# nucleum.net
KiCad netlist of a schematic drawn in EAGLE
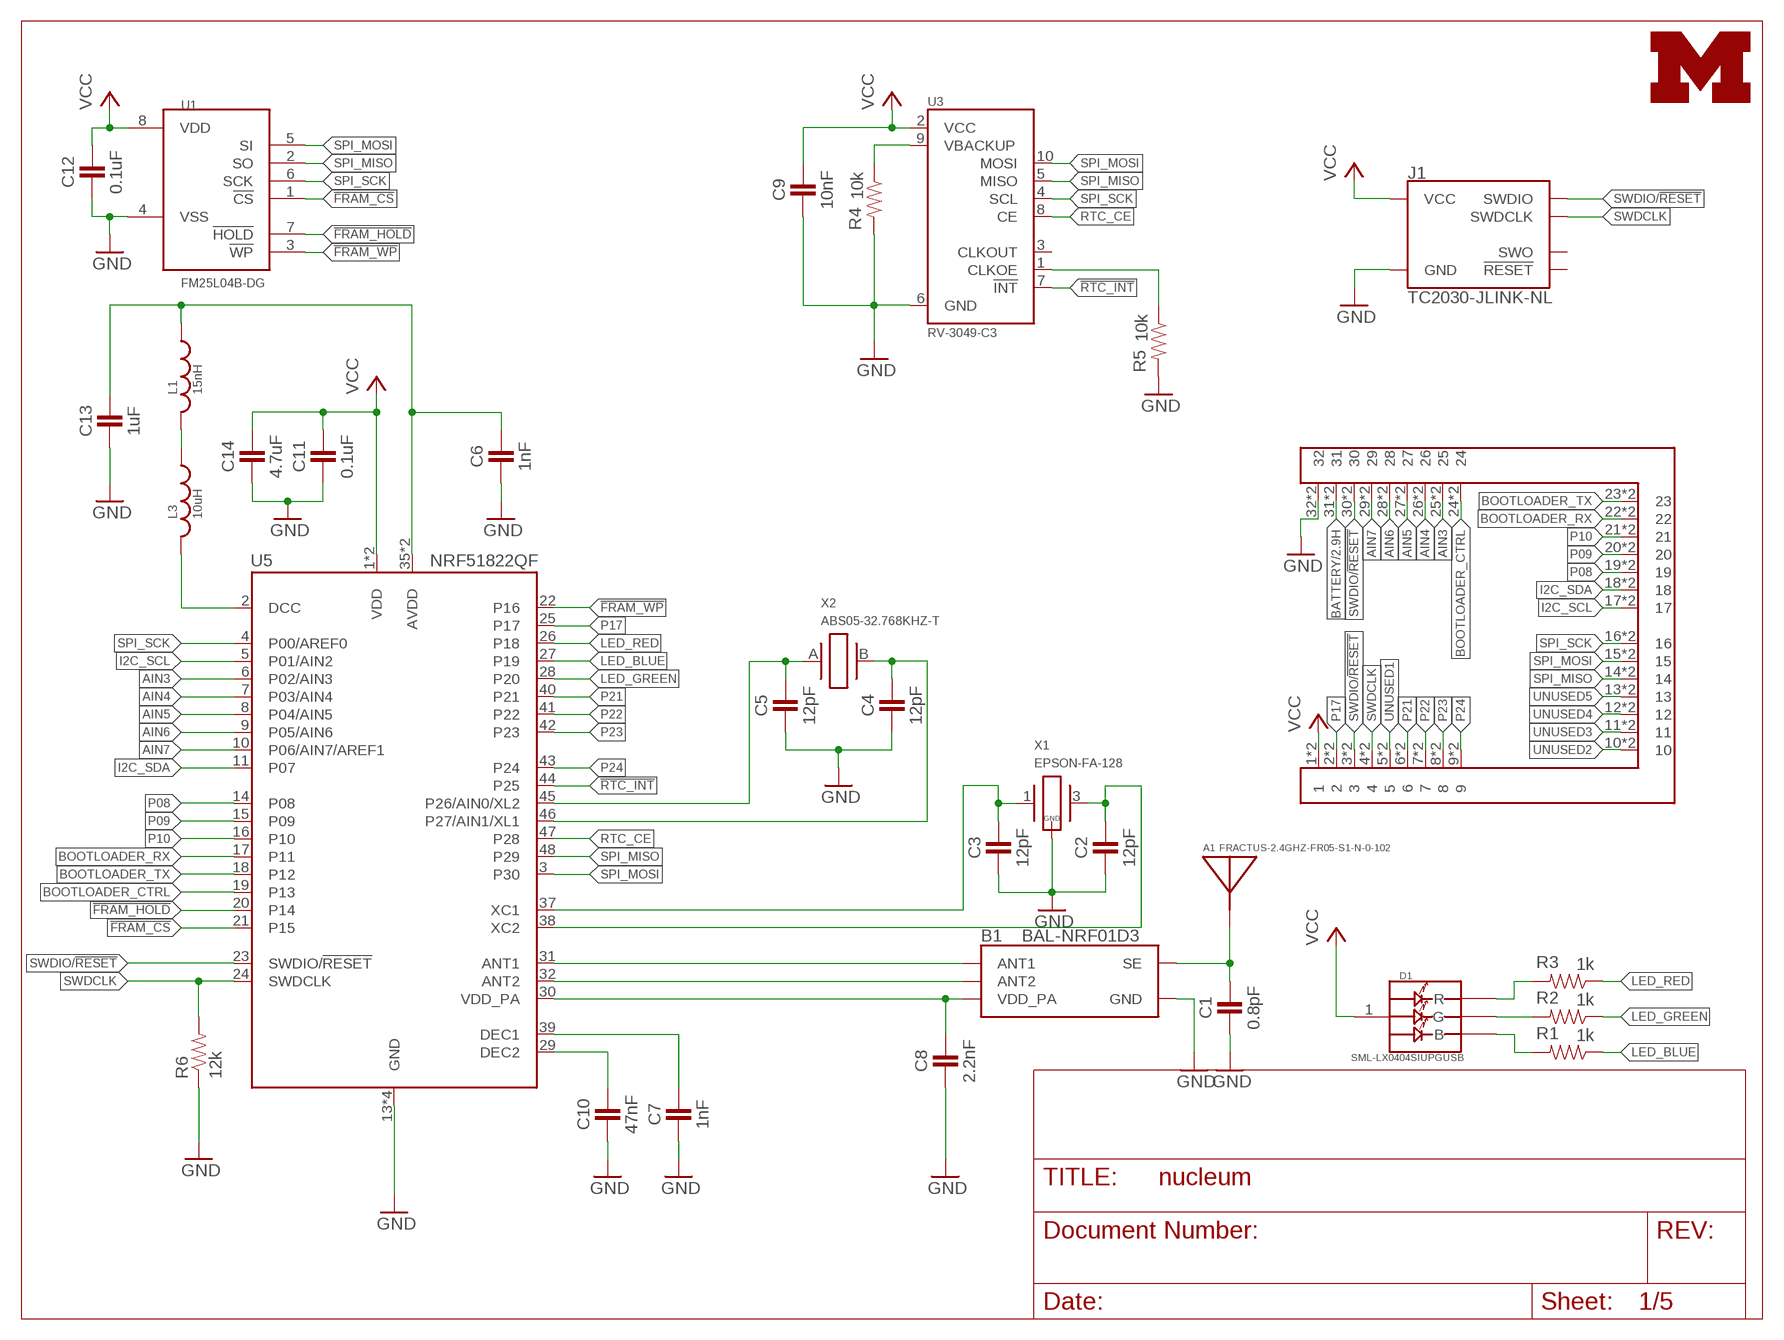
[diagram p0: schematic, sheet 1]
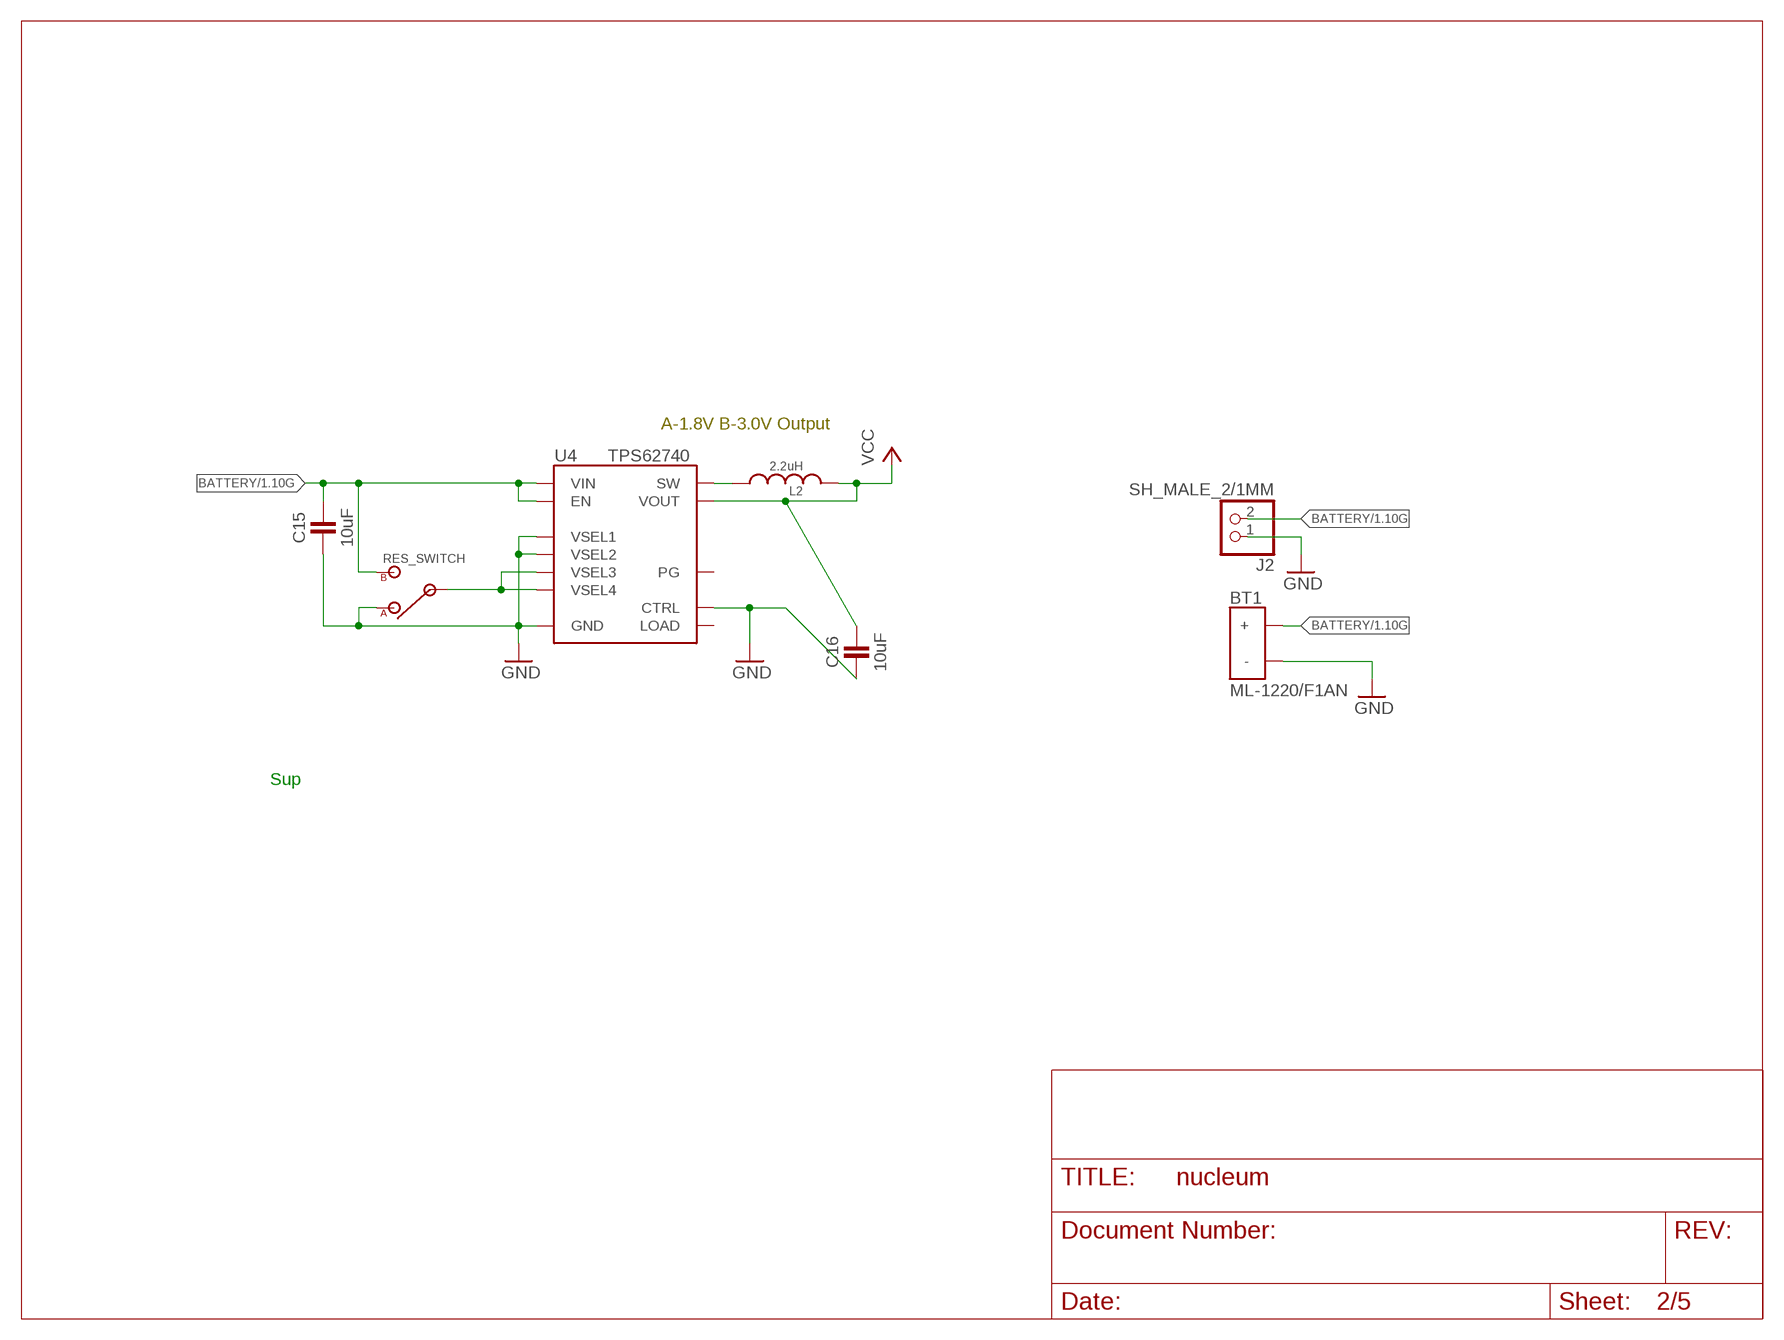
[diagram p1: schematic, sheet 2]
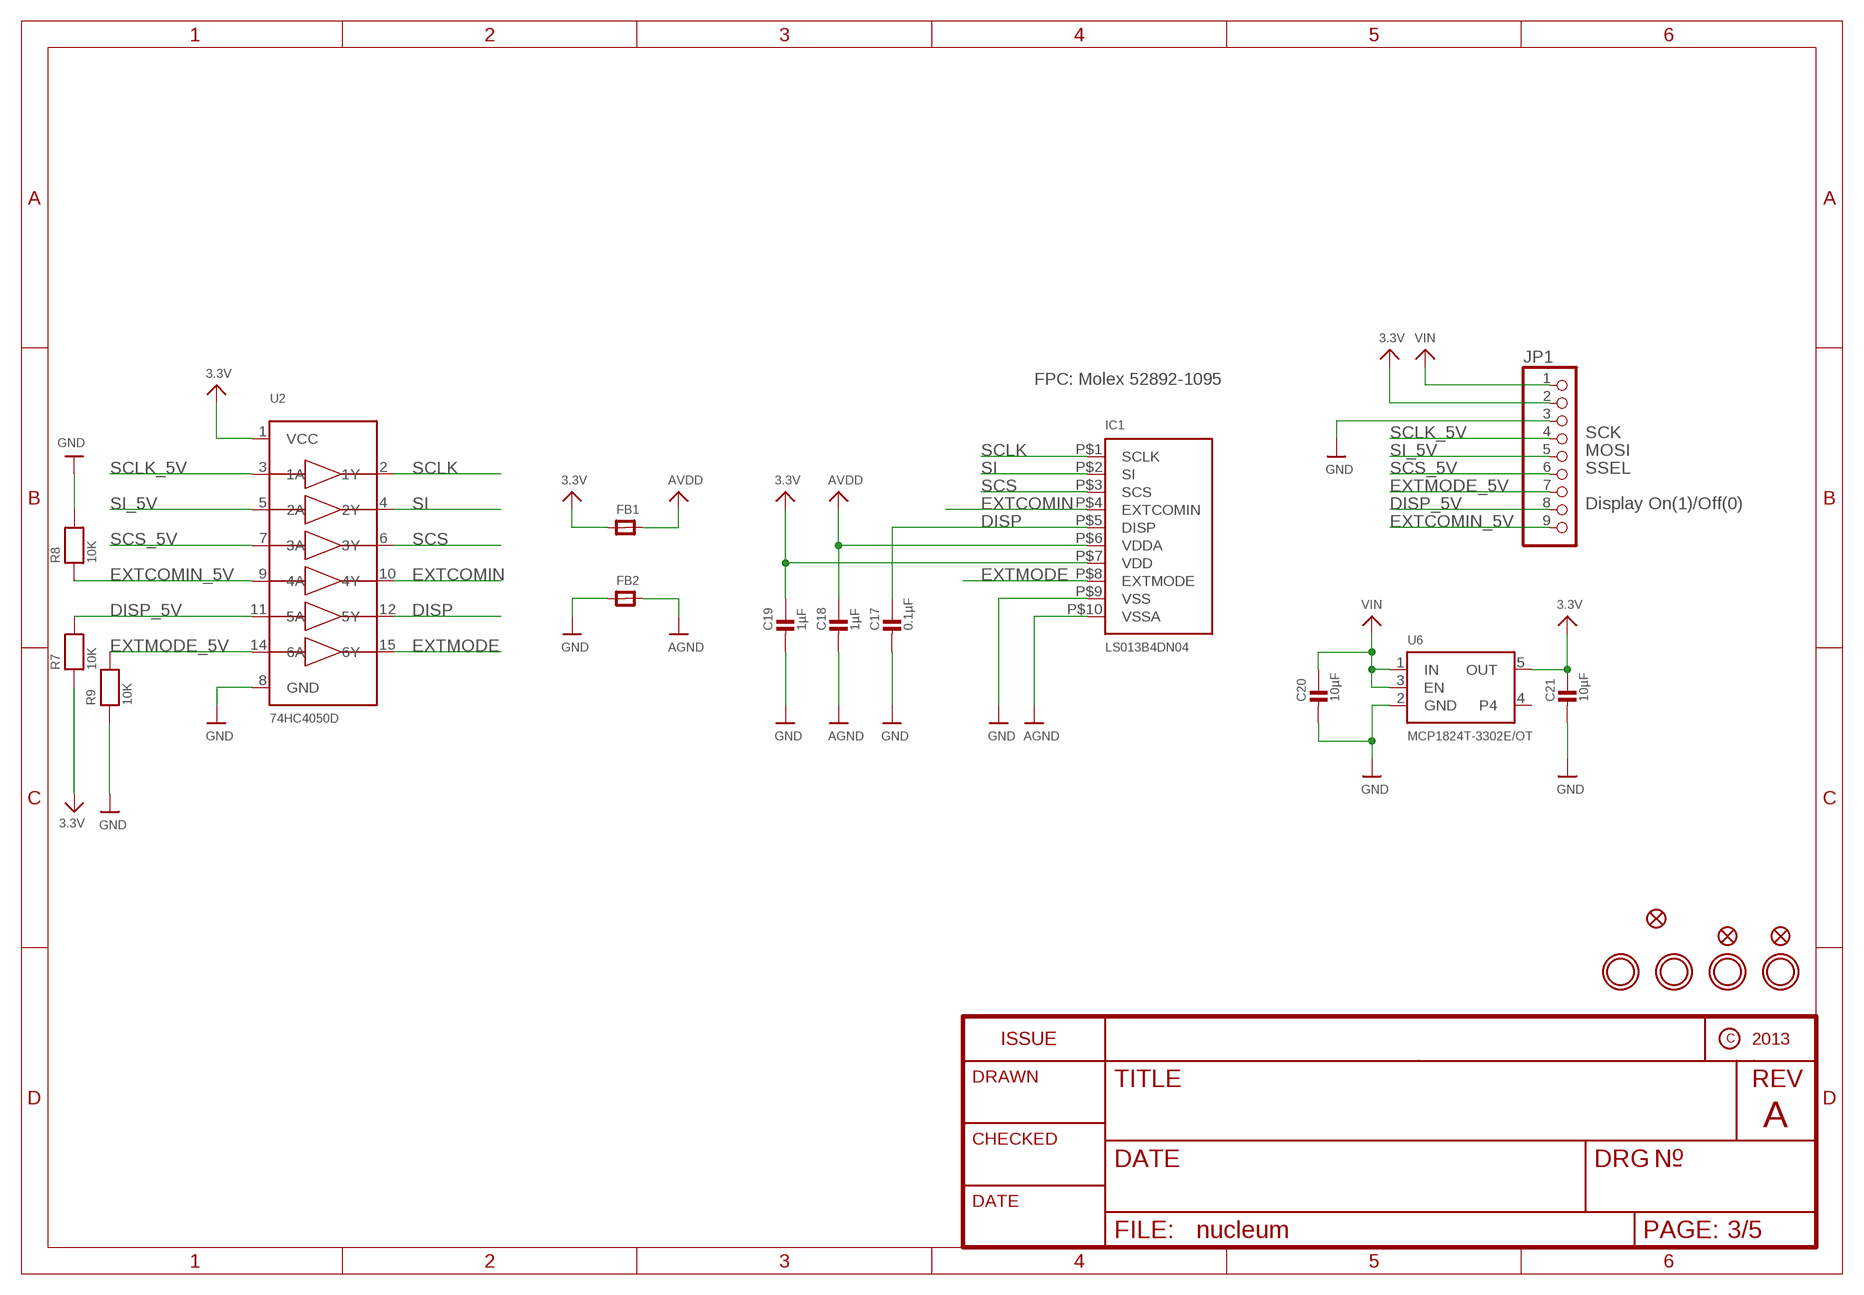
[diagram p2: schematic, sheet 3]
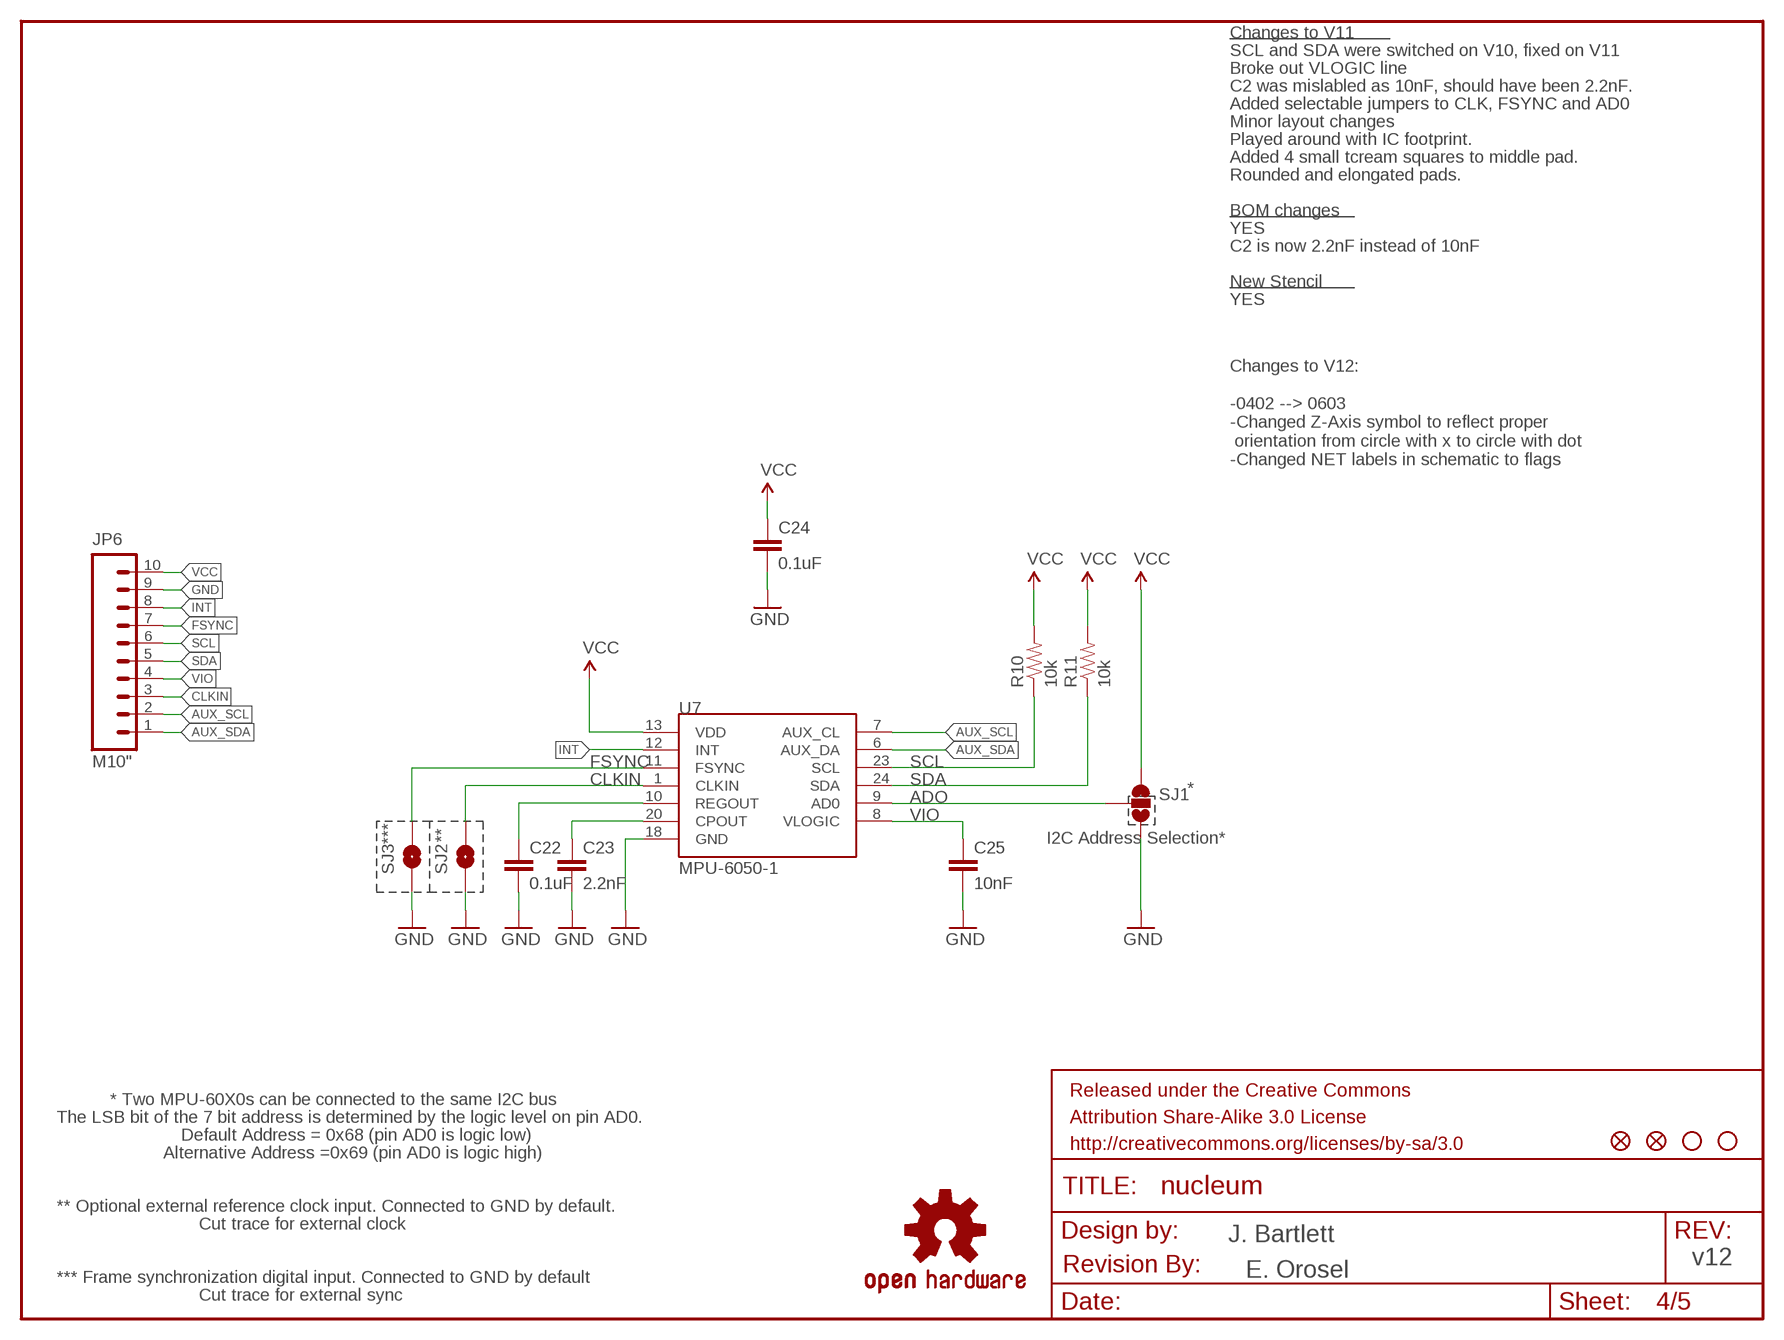
[diagram p3: schematic, sheet 4]

(export (version "E")
  (design (tool "Eeschema 10.0.6"))
  (components
    (comp (ref "C17")
      (value "0.1µF")
      (footprint "eagle-import:_0805")
      (libsource (lib "eagle-import") (part "CAP_CERAMIC_0805"))
    )
    (comp (ref "C18")
      (value "1µF")
      (footprint "eagle-import:_0805")
      (libsource (lib "eagle-import") (part "CAP_CERAMIC_0805"))
    )
    (comp (ref "C19")
      (value "1µF")
      (footprint "eagle-import:_0805")
      (libsource (lib "eagle-import") (part "CAP_CERAMIC_0805"))
    )
    (comp (ref "C20")
      (value "10µF")
      (footprint "eagle-import:_0805")
      (libsource (lib "eagle-import") (part "CAP_CERAMIC_0805"))
    )
    (comp (ref "C21")
      (value "10µF")
      (footprint "eagle-import:_0805")
      (libsource (lib "eagle-import") (part "CAP_CERAMIC_0805"))
    )
    (comp (ref "FB1")
      (value "FERRITE_0805")
      (footprint "eagle-import:_0805")
      (libsource (lib "eagle-import") (part "FERRITE_0805"))
    )
    (comp (ref "FB2")
      (value "FERRITE_0805")
      (footprint "eagle-import:_0805")
      (libsource (lib "eagle-import") (part "FERRITE_0805"))
    )
    (comp (ref "FID1")
      (value "FIDUCIAL\"\"")
      (footprint "eagle-import:FIDUCIAL_1MM")
      (libsource (lib "eagle-import") (part "FIDUCIAL{dblquote}{dblquote}"))
    )
    (comp (ref "FID2")
      (value "FIDUCIAL\"\"")
      (footprint "eagle-import:FIDUCIAL_1MM")
      (libsource (lib "eagle-import") (part "FIDUCIAL{dblquote}{dblquote}"))
    )
    (comp (ref "FID3")
      (value "FIDUCIAL\"\"")
      (footprint "eagle-import:FIDUCIAL_1MM")
      (libsource (lib "eagle-import") (part "FIDUCIAL{dblquote}{dblquote}"))
    )
    (comp (ref "IC1")
      (value "LS013B4DN04")
      (footprint "eagle-import:FPC_10PIN_52892-1095")
      (libsource (lib "eagle-import") (part "SHARP_MEMORYLCD_10PIN"))
    )
    (comp (ref "JP1")
      (value "HEADER-1X970MIL")
      (footprint "eagle-import:1X09_ROUND_70")
      (libsource (lib "eagle-import") (part "HEADER-1X970MIL"))
    )
    (comp (ref "R7")
      (value "10K")
      (footprint "eagle-import:_0805")
      (libsource (lib "eagle-import") (part "RESISTOR_0805"))
    )
    (comp (ref "R8")
      (value "10K")
      (footprint "eagle-import:_0805")
      (libsource (lib "eagle-import") (part "RESISTOR_0805"))
    )
    (comp (ref "R9")
      (value "10K")
      (footprint "eagle-import:_0805")
      (libsource (lib "eagle-import") (part "RESISTOR_0805"))
    )
    (comp (ref "U$21")
      (value "MOUNTINGHOLE3.0THIN")
      (footprint "eagle-import:MOUNTINGHOLE_3.0_PLATEDTHIN")
      (libsource (lib "eagle-import") (part "MOUNTINGHOLE3.0THIN"))
    )
    (comp (ref "U$22")
      (value "MOUNTINGHOLE3.0THIN")
      (footprint "eagle-import:MOUNTINGHOLE_3.0_PLATEDTHIN")
      (libsource (lib "eagle-import") (part "MOUNTINGHOLE3.0THIN"))
    )
    (comp (ref "U$27")
      (value "MOUNTINGHOLE3.0THIN")
      (footprint "eagle-import:MOUNTINGHOLE_3.0_PLATEDTHIN")
      (libsource (lib "eagle-import") (part "MOUNTINGHOLE3.0THIN"))
    )
    (comp (ref "U$28")
      (value "MOUNTINGHOLE3.0THIN")
      (footprint "eagle-import:MOUNTINGHOLE_3.0_PLATEDTHIN")
      (libsource (lib "eagle-import") (part "MOUNTINGHOLE3.0THIN"))
    )
    (comp (ref "U2")
      (value "74HC4050D")
      (footprint "eagle-import:SOIC16")
      (libsource (lib "eagle-import") (part "74HC4050D"))
    )
    (comp (ref "U6")
      (value "MCP1824T-3302E/OT")
      (footprint "eagle-import:SOT23-5")
      (libsource (lib "eagle-import") (part "VREG_SOT23-5"))
    )
    (comp (ref "C22")
      (value "0.1uF")
      (footprint "eagle-import:0603-CAP")
      (libsource (lib "eagle-import") (part "CAP0603-CAP"))
    )
    (comp (ref "C23")
      (value "2.2nF")
      (footprint "eagle-import:0603-CAP")
      (libsource (lib "eagle-import") (part "CAP0603-CAP"))
    )
    (comp (ref "C24")
      (value "0.1uF")
      (footprint "eagle-import:0603-CAP")
      (libsource (lib "eagle-import") (part "CAP0603-CAP"))
    )
    (comp (ref "C25")
      (value "10nF")
      (footprint "eagle-import:0603-CAP")
      (libsource (lib "eagle-import") (part "CAP0603-CAP"))
    )
    (comp (ref "FRAME4")
      (value "FRAME-LETTER")
      (footprint "eagle-import:CREATIVE_COMMONS")
      (libsource (lib "eagle-import") (part "FRAME-LETTER"))
    )
    (comp (ref "JP2")
      (value "FIDUCIALUFIDUCIAL")
      (footprint "eagle-import:MICRO-FIDUCIAL")
      (libsource (lib "eagle-import") (part "FIDUCIALUFIDUCIAL"))
    )
    (comp (ref "JP3")
      (value "STAND-OFFTIGHT")
      (footprint "eagle-import:STAND-OFF-TIGHT")
      (libsource (lib "eagle-import") (part "STAND-OFFTIGHT"))
    )
    (comp (ref "JP4")
      (value "STAND-OFFTIGHT")
      (footprint "eagle-import:STAND-OFF-TIGHT")
      (libsource (lib "eagle-import") (part "STAND-OFFTIGHT"))
    )
    (comp (ref "JP5")
      (value "FIDUCIALUFIDUCIAL")
      (footprint "eagle-import:MICRO-FIDUCIAL")
      (libsource (lib "eagle-import") (part "FIDUCIALUFIDUCIAL"))
    )
    (comp (ref "JP6")
      (value "M10\"")
      (footprint "eagle-import:1X10")
      (libsource (lib "eagle-import") (part "M10{dblquote}"))
    )
    (comp (ref "R10")
      (value "10k")
      (footprint "eagle-import:0603-RES")
      (libsource (lib "eagle-import") (part "RESISTOR0603-RES"))
    )
    (comp (ref "R11")
      (value "10k")
      (footprint "eagle-import:0603-RES")
      (libsource (lib "eagle-import") (part "RESISTOR0603-RES"))
    )
    (comp (ref "SJ1")
      (value "SOLDERJUMPER_2WAYPASTE2&3")
      (footprint "eagle-import:SJ_3_PASTE2&3")
      (libsource (lib "eagle-import") (part "SOLDERJUMPER_2WAYPASTE2&3"))
    )
    (comp (ref "SJ2")
      (value "SOLDERJUMPERTRACE")
      (footprint "eagle-import:SJ_2S-TRACE")
      (libsource (lib "eagle-import") (part "SOLDERJUMPERTRACE"))
    )
    (comp (ref "SJ3")
      (value "SOLDERJUMPERTRACE")
      (footprint "eagle-import:SJ_2S-TRACE")
      (libsource (lib "eagle-import") (part "SOLDERJUMPERTRACE"))
    )
    (comp (ref "U$30")
      (value "OSHW-LOGOS")
      (footprint "eagle-import:OSHW-LOGO-S")
      (libsource (lib "eagle-import") (part "OSHW-LOGOS"))
    )
    (comp (ref "U$31")
      (value "REVISION")
      (footprint "eagle-import:REVISION")
      (libsource (lib "eagle-import") (part "REVISION"))
    )
    (comp (ref "U7")
      (value "MPU-6050-1")
      (footprint "eagle-import:QFN-24-4MM2")
      (libsource (lib "eagle-import") (part "MPU-6050-1"))
    )
    (comp (ref "A1")
      (value "FRACTUS-2.4GHZ-FR05-S1-N-0-102")
      (footprint "eagle-import:FRACTUS-ANTENNA-FR05-S1-N-0-102")
      (libsource (lib "eagle-import") (part "FRACTUS-2.4GHZ-FR05-S1-N-0-102"))
    )
    (comp (ref "B1")
      (value "BAL-NRF01D3")
      (footprint "eagle-import:BAL-NRF01D3")
      (libsource (lib "eagle-import") (part "BAL-NRF01D3"))
    )
    (comp (ref "C1")
      (value "0.8pF")
      (footprint "eagle-import:0402_CAP")
      (libsource (lib "eagle-import") (part "CAPACITOR"))
    )
    (comp (ref "C2")
      (value "12pF")
      (footprint "eagle-import:0402_CAP")
      (libsource (lib "eagle-import") (part "CAPACITOR"))
    )
    (comp (ref "C3")
      (value "12pF")
      (footprint "eagle-import:0402_CAP")
      (libsource (lib "eagle-import") (part "CAPACITOR"))
    )
    (comp (ref "C4")
      (value "12pF")
      (footprint "eagle-import:0402_CAP")
      (libsource (lib "eagle-import") (part "CAPACITOR"))
    )
    (comp (ref "C5")
      (value "12pF")
      (footprint "eagle-import:0402_CAP")
      (libsource (lib "eagle-import") (part "CAPACITOR"))
    )
    (comp (ref "C6")
      (value "1nF")
      (footprint "eagle-import:0402_CAP")
      (libsource (lib "eagle-import") (part "CAPACITOR"))
    )
    (comp (ref "C7")
      (value "1nF")
      (footprint "eagle-import:0402_CAP")
      (libsource (lib "eagle-import") (part "CAPACITOR"))
    )
    (comp (ref "C8")
      (value "2.2nF")
      (footprint "eagle-import:0402_CAP")
      (libsource (lib "eagle-import") (part "CAPACITOR"))
    )
    (comp (ref "C9")
      (value "10nF")
      (footprint "eagle-import:0402_CAP")
      (libsource (lib "eagle-import") (part "CAPACITOR"))
    )
    (comp (ref "C10")
      (value "47nF")
      (footprint "eagle-import:0402_CAP")
      (libsource (lib "eagle-import") (part "CAPACITOR"))
    )
    (comp (ref "C11")
      (value "0.1uF")
      (footprint "eagle-import:0402_CAP")
      (libsource (lib "eagle-import") (part "CAPACITOR"))
    )
    (comp (ref "C12")
      (value "0.1uF")
      (footprint "eagle-import:0402_CAP")
      (libsource (lib "eagle-import") (part "CAPACITOR"))
    )
    (comp (ref "C13")
      (value "1uF")
      (footprint "eagle-import:0402_CAP")
      (libsource (lib "eagle-import") (part "CAPACITOR"))
    )
    (comp (ref "C14")
      (value "4.7uF")
      (footprint "eagle-import:0402_CAP")
      (libsource (lib "eagle-import") (part "CAPACITOR"))
    )
    (comp (ref "D1")
      (value "SML-LX0404SIUPGUSB")
      (footprint "eagle-import:1MM_SQ_4PAD")
      (libsource (lib "eagle-import") (part "SML-LX0404SIUPGUSB"))
    )
    (comp (ref "J1")
      (value "TC2030-JLINK-NL")
      (footprint "eagle-import:TC2030-IDC-NL")
      (libsource (lib "eagle-import") (part "TC2030-JLINK-NL"))
    )
    (comp (ref "J3")
      (value "ATUM-HEADER")
      (footprint "eagle-import:ATUM-HEADER")
      (libsource (lib "eagle-import") (part "ATUM-HEADER"))
    )
    (comp (ref "L1")
      (value "15nH")
      (footprint "eagle-import:0402_CAP")
      (libsource (lib "eagle-import") (part "INDUCTOR0402"))
    )
    (comp (ref "L3")
      (value "10uH")
      (footprint "eagle-import:0603_CAP")
      (libsource (lib "eagle-import") (part "INDUCTOR0603"))
    )
    (comp (ref "LOGO1")
      (value "UMICH_SOLID_TINY")
      (footprint "eagle-import:UMICH_SOLID_50MIL")
      (libsource (lib "eagle-import") (part "UMICH_SOLID_TINY"))
    )
    (comp (ref "R1")
      (value "1k")
      (footprint "eagle-import:0402_RES")
      (libsource (lib "eagle-import") (part "RESISTOR0402_RES"))
    )
    (comp (ref "R2")
      (value "1k")
      (footprint "eagle-import:0402_RES")
      (libsource (lib "eagle-import") (part "RESISTOR0402_RES"))
    )
    (comp (ref "R3")
      (value "1k")
      (footprint "eagle-import:0402_RES")
      (libsource (lib "eagle-import") (part "RESISTOR0402_RES"))
    )
    (comp (ref "R4")
      (value "10k")
      (footprint "eagle-import:0402_RES")
      (libsource (lib "eagle-import") (part "RESISTOR0402_RES"))
    )
    (comp (ref "R5")
      (value "10k")
      (footprint "eagle-import:0402_RES")
      (libsource (lib "eagle-import") (part "RESISTOR0402_RES"))
    )
    (comp (ref "R6")
      (value "12k")
      (footprint "eagle-import:0402_RES")
      (libsource (lib "eagle-import") (part "RESISTOR0402_RES"))
    )
    (comp (ref "U1")
      (value "FM25L04B-DG")
      (footprint "eagle-import:TDFN-8")
      (libsource (lib "eagle-import") (part "FM25L04B-DG"))
    )
    (comp (ref "U3")
      (value "RV-3049-C3")
      (footprint "eagle-import:MICRO-CRYSTAL-C3")
      (libsource (lib "eagle-import") (part "RV-3049-C3"))
    )
    (comp (ref "U5")
      (value "NRF51822QF")
      (footprint "eagle-import:QFN-48-6MM")
      (libsource (lib "eagle-import") (part "NRF51822QF"))
    )
    (comp (ref "X1")
      (value "EPSON-FA-128")
      (footprint "eagle-import:FA-128")
      (libsource (lib "eagle-import") (part "EPSON-FA-128"))
    )
    (comp (ref "X2")
      (value "ABS05-32.768KHZ-T")
      (footprint "eagle-import:ABS05")
      (libsource (lib "eagle-import") (part "ABS05-32.768KHZ-T"))
    )
    (comp (ref "BT1")
      (value "ML-1220/F1AN")
      (footprint "eagle-import:ML-1220_F1BN")
      (libsource (lib "eagle-import") (part "ML-1220/F1AN"))
    )
    (comp (ref "C15")
      (value "10uF")
      (footprint "eagle-import:0603_CAP")
      (libsource (lib "eagle-import") (part "CAPACITOR0603_CAP"))
    )
    (comp (ref "C16")
      (value "10uF")
      (footprint "eagle-import:0603_CAP")
      (libsource (lib "eagle-import") (part "CAPACITOR0603_CAP"))
    )
    (comp (ref "J2")
      (value "SH_MALE_2/1MM")
      (footprint "eagle-import:SH-1X2_1MM")
      (libsource (lib "eagle-import") (part "SH_MALE_2/1MM"))
    )
    (comp (ref "L2")
      (value "2.2uH")
      (footprint "eagle-import:MIPSZ201D")
      (libsource (lib "eagle-import") (part "MIPSZ2012D"))
    )
    (comp (ref "S1")
      (value "RES_SWITCH")
      (footprint "eagle-import:RES_SWITCH")
      (libsource (lib "eagle-import") (part "RES_SWITCH"))
    )
    (comp (ref "U4")
      (value "TPS62740")
      (footprint "eagle-import:R-PWSON-12")
      (libsource (lib "eagle-import") (part "TPS62740"))
    )
  )
  (nets
    (net (code "1") (name "3.3V") (class "Default")
      (node (ref "C19") (pin "1") (pinfunction "P$1_1") (pintype "passive"))
      (node (ref "C21") (pin "1") (pinfunction "P$1_1") (pintype "passive"))
      (node (ref "FB1") (pin "1") (pinfunction "P$1_1") (pintype "passive"))
      (node (ref "IC1") (pin "P$7") (pinfunction "VDD_P$7") (pintype "power_in"))
      (node (ref "JP1") (pin "2") (pinfunction "2_2") (pintype "passive"))
      (node (ref "R7") (pin "1") (pinfunction "1_1") (pintype "passive"))
      (node (ref "U2") (pin "1") (pinfunction "VCC_1") (pintype "bidirectional"))
      (node (ref "U6") (pin "5") (pinfunction "OUT_5") (pintype "power_in"))
    )
    (net (code "2") (name "ADO") (class "Default")
      (node (ref "SJ1") (pin "2") (pinfunction "2_2") (pintype "passive"))
      (node (ref "U7") (pin "9") (pinfunction "AD0_9") (pintype "bidirectional"))
    )
    (net (code "3") (name "AGND") (class "Default")
      (node (ref "C18") (pin "2") (pinfunction "P$2_2") (pintype "passive"))
      (node (ref "FB2") (pin "2") (pinfunction "P$2_2") (pintype "passive"))
      (node (ref "IC1") (pin "P$10") (pinfunction "VSSA_P$10") (pintype "power_in"))
    )
    (net (code "4") (name "AIN3") (class "Default")
      (node (ref "J3") (pin "25") (pinfunction "25_25") (pintype "bidirectional"))
      (node (ref "J3") (pin "25B") (pinfunction "25_25B") (pintype "bidirectional"))
      (node (ref "U5") (pin "6") (pinfunction "P02/AIN3_6") (pintype "bidirectional"))
    )
    (net (code "5") (name "AIN4") (class "Default")
      (node (ref "J3") (pin "26") (pinfunction "26_26") (pintype "bidirectional"))
      (node (ref "J3") (pin "26B") (pinfunction "26_26B") (pintype "bidirectional"))
      (node (ref "U5") (pin "7") (pinfunction "P03/AIN4_7") (pintype "bidirectional"))
    )
    (net (code "6") (name "AIN5") (class "Default")
      (node (ref "J3") (pin "27") (pinfunction "27_27") (pintype "bidirectional"))
      (node (ref "J3") (pin "27B") (pinfunction "27_27B") (pintype "bidirectional"))
      (node (ref "U5") (pin "8") (pinfunction "P04/AIN5_8") (pintype "bidirectional"))
    )
    (net (code "7") (name "AIN6") (class "Default")
      (node (ref "J3") (pin "28") (pinfunction "28_28") (pintype "bidirectional"))
      (node (ref "J3") (pin "28B") (pinfunction "28_28B") (pintype "bidirectional"))
      (node (ref "U5") (pin "9") (pinfunction "P05/AIN6_9") (pintype "bidirectional"))
    )
    (net (code "8") (name "AIN7") (class "Default")
      (node (ref "J3") (pin "29") (pinfunction "29_29") (pintype "bidirectional"))
      (node (ref "J3") (pin "29B") (pinfunction "29_29B") (pintype "bidirectional"))
      (node (ref "U5") (pin "10") (pinfunction "P06/AIN7/AREF1_10") (pintype "bidirectional"))
    )
    (net (code "9") (name "AUX_SCL") (class "Default")
      (node (ref "JP6") (pin "2") (pinfunction "2_2") (pintype "passive"))
      (node (ref "U7") (pin "7") (pinfunction "AUX_CL_7") (pintype "bidirectional"))
    )
    (net (code "10") (name "AUX_SDA") (class "Default")
      (node (ref "JP6") (pin "1") (pinfunction "1_1") (pintype "passive"))
      (node (ref "U7") (pin "6") (pinfunction "AUX_DA_6") (pintype "bidirectional"))
    )
    (net (code "11") (name "AVDD") (class "Default")
      (node (ref "C18") (pin "1") (pinfunction "P$1_1") (pintype "passive"))
      (node (ref "FB1") (pin "2") (pinfunction "P$2_2") (pintype "passive"))
      (node (ref "IC1") (pin "P$6") (pinfunction "VDDA_P$6") (pintype "power_in"))
    )
    (net (code "12") (name "BATTERY") (class "Default")
      (node (ref "BT1") (pin "POS") (pinfunction "+_POS") (pintype "bidirectional"))
      (node (ref "C15") (pin "1") (pinfunction "1_1") (pintype "bidirectional"))
      (node (ref "J2") (pin "2") (pinfunction "2_2") (pintype "passive"))
      (node (ref "J3") (pin "31") (pinfunction "31_31") (pintype "bidirectional"))
      (node (ref "J3") (pin "31B") (pinfunction "31_31B") (pintype "bidirectional"))
      (node (ref "S1") (pin "B") (pinfunction "B_B") (pintype "bidirectional"))
      (node (ref "U4") (pin "1") (pinfunction "VIN_1") (pintype "bidirectional"))
      (node (ref "U4") (pin "12") (pinfunction "EN_12") (pintype "bidirectional"))
    )
    (net (code "13") (name "BOOTLOADER_CTRL") (class "Default")
      (node (ref "J3") (pin "24") (pinfunction "24_24") (pintype "bidirectional"))
      (node (ref "J3") (pin "24B") (pinfunction "24_24B") (pintype "bidirectional"))
      (node (ref "U5") (pin "19") (pinfunction "P13_19") (pintype "bidirectional"))
    )
    (net (code "14") (name "BOOTLOADER_RX") (class "Default")
      (node (ref "J3") (pin "22") (pinfunction "22_22") (pintype "bidirectional"))
      (node (ref "J3") (pin "22B") (pinfunction "22_22B") (pintype "bidirectional"))
      (node (ref "U5") (pin "17") (pinfunction "P11_17") (pintype "bidirectional"))
    )
    (net (code "15") (name "BOOTLOADER_TX") (class "Default")
      (node (ref "J3") (pin "23") (pinfunction "23_23") (pintype "bidirectional"))
      (node (ref "J3") (pin "23B") (pinfunction "23_23B") (pintype "bidirectional"))
      (node (ref "U5") (pin "18") (pinfunction "P12_18") (pintype "bidirectional"))
    )
    (net (code "16") (name "CLKIN") (class "Default")
      (node (ref "JP6") (pin "3") (pinfunction "3_3") (pintype "passive"))
      (node (ref "SJ2") (pin "2") (pinfunction "2_2") (pintype "passive"))
      (node (ref "U7") (pin "1") (pinfunction "CLKIN_1") (pintype "bidirectional"))
    )
    (net (code "17") (name "DISP") (class "Default")
      (node (ref "C17") (pin "1") (pinfunction "P$1_1") (pintype "passive"))
      (node (ref "IC1") (pin "P$5") (pinfunction "DISP_P$5") (pintype "input"))
      (node (ref "U2") (pin "12") (pinfunction "5Y_12") (pintype "bidirectional"))
    )
    (net (code "18") (name "DISP_5V") (class "Default")
      (node (ref "JP1") (pin "8") (pinfunction "8_8") (pintype "passive"))
      (node (ref "R7") (pin "2") (pinfunction "2_2") (pintype "passive"))
      (node (ref "U2") (pin "11") (pinfunction "5A_11") (pintype "bidirectional"))
    )
    (net (code "19") (name "EXTCOMIN") (class "Default")
      (node (ref "IC1") (pin "P$4") (pinfunction "EXTCOMIN_P$4") (pintype "input"))
      (node (ref "U2") (pin "10") (pinfunction "4Y_10") (pintype "bidirectional"))
    )
    (net (code "20") (name "EXTCOMIN_5V") (class "Default")
      (node (ref "JP1") (pin "9") (pinfunction "9_9") (pintype "passive"))
      (node (ref "R8") (pin "1") (pinfunction "1_1") (pintype "passive"))
      (node (ref "U2") (pin "9") (pinfunction "4A_9") (pintype "bidirectional"))
    )
    (net (code "21") (name "EXTMODE") (class "Default")
      (node (ref "IC1") (pin "P$8") (pinfunction "EXTMODE_P$8") (pintype "input"))
      (node (ref "U2") (pin "15") (pinfunction "6Y_15") (pintype "bidirectional"))
    )
    (net (code "22") (name "EXTMODE_5V") (class "Default")
      (node (ref "JP1") (pin "7") (pinfunction "7_7") (pintype "passive"))
      (node (ref "R9") (pin "2") (pinfunction "2_2") (pintype "passive"))
      (node (ref "U2") (pin "14") (pinfunction "6A_14") (pintype "bidirectional"))
    )
    (net (code "23") (name "FSYNC") (class "Default")
      (node (ref "JP6") (pin "7") (pinfunction "7_7") (pintype "passive"))
      (node (ref "SJ3") (pin "2") (pinfunction "2_2") (pintype "passive"))
      (node (ref "U7") (pin "11") (pinfunction "FSYNC_11") (pintype "bidirectional"))
    )
    (net (code "24") (name "GND") (class "Default")
      (node (ref "B1") (pin "GND") (pinfunction "GND_GND") (pintype "bidirectional"))
      (node (ref "BT1") (pin "NEG") (pinfunction "-_NEG") (pintype "bidirectional"))
      (node (ref "C1") (pin "2") (pinfunction "2_2") (pintype "bidirectional"))
      (node (ref "C10") (pin "2") (pinfunction "2_2") (pintype "bidirectional"))
      (node (ref "C11") (pin "2") (pinfunction "2_2") (pintype "bidirectional"))
      (node (ref "C12") (pin "2") (pinfunction "2_2") (pintype "bidirectional"))
      (node (ref "C13") (pin "2") (pinfunction "2_2") (pintype "bidirectional"))
      (node (ref "C14") (pin "2") (pinfunction "2_2") (pintype "bidirectional"))
      (node (ref "C15") (pin "2") (pinfunction "2_2") (pintype "bidirectional"))
      (node (ref "C16") (pin "2") (pinfunction "2_2") (pintype "bidirectional"))
      (node (ref "C17") (pin "2") (pinfunction "P$2_2") (pintype "passive"))
      (node (ref "C19") (pin "2") (pinfunction "P$2_2") (pintype "passive"))
      (node (ref "C2") (pin "2") (pinfunction "2_2") (pintype "bidirectional"))
      (node (ref "C20") (pin "2") (pinfunction "P$2_2") (pintype "passive"))
      (node (ref "C21") (pin "2") (pinfunction "P$2_2") (pintype "passive"))
      (node (ref "C22") (pin "2") (pinfunction "2_2") (pintype "passive"))
      (node (ref "C23") (pin "2") (pinfunction "2_2") (pintype "passive"))
      (node (ref "C24") (pin "2") (pinfunction "2_2") (pintype "passive"))
      (node (ref "C25") (pin "2") (pinfunction "2_2") (pintype "passive"))
      (node (ref "C3") (pin "2") (pinfunction "2_2") (pintype "bidirectional"))
      (node (ref "C4") (pin "2") (pinfunction "2_2") (pintype "bidirectional"))
      (node (ref "C5") (pin "2") (pinfunction "2_2") (pintype "bidirectional"))
      (node (ref "C6") (pin "2") (pinfunction "2_2") (pintype "bidirectional"))
      (node (ref "C7") (pin "2") (pinfunction "2_2") (pintype "bidirectional"))
      (node (ref "C8") (pin "2") (pinfunction "2_2") (pintype "bidirectional"))
      (node (ref "C9") (pin "2") (pinfunction "2_2") (pintype "bidirectional"))
      (node (ref "FB2") (pin "1") (pinfunction "P$1_1") (pintype "passive"))
      (node (ref "IC1") (pin "P$9") (pinfunction "VSS_P$9") (pintype "power_in"))
      (node (ref "J1") (pin "5") (pinfunction "GND_5") (pintype "bidirectional"))
      (node (ref "J2") (pin "1") (pinfunction "1_1") (pintype "passive"))
      (node (ref "J3") (pin "32") (pinfunction "32_32") (pintype "bidirectional"))
      (node (ref "J3") (pin "32B") (pinfunction "32_32B") (pintype "bidirectional"))
      (node (ref "JP1") (pin "3") (pinfunction "3_3") (pintype "passive"))
      (node (ref "JP6") (pin "9") (pinfunction "9_9") (pintype "passive"))
      (node (ref "R4") (pin "2") (pinfunction "2_2") (pintype "passive"))
      (node (ref "R5") (pin "2") (pinfunction "2_2") (pintype "passive"))
      (node (ref "R6") (pin "1") (pinfunction "1_1") (pintype "passive"))
      (node (ref "R8") (pin "2") (pinfunction "2_2") (pintype "passive"))
      (node (ref "R9") (pin "1") (pinfunction "1_1") (pintype "passive"))
      (node (ref "S1") (pin "A") (pinfunction "A_A") (pintype "bidirectional"))
      (node (ref "SJ1") (pin "3") (pinfunction "3_3") (pintype "passive"))
      (node (ref "SJ2") (pin "1") (pinfunction "1_1") (pintype "passive"))
      (node (ref "SJ3") (pin "1") (pinfunction "1_1") (pintype "passive"))
      (node (ref "U1") (pin "4") (pinfunction "VSS_4") (pintype "bidirectional"))
      (node (ref "U2") (pin "8") (pinfunction "GND_8") (pintype "bidirectional"))
      (node (ref "U3") (pin "6") (pinfunction "GND_6") (pintype "bidirectional"))
      (node (ref "U4") (pin "10") (pinfunction "VSEL2_10") (pintype "bidirectional"))
      (node (ref "U4") (pin "11") (pinfunction "VSEL1_11") (pintype "bidirectional"))
      (node (ref "U4") (pin "3") (pinfunction "GND_3") (pintype "bidirectional"))
      (node (ref "U4") (pin "4") (pinfunction "CTRL_4") (pintype "bidirectional"))
      (node (ref "U4") (pin "NC") (pinfunction "GND_NC") (pintype "bidirectional"))
      (node (ref "U5") (pin "13") (pinfunction "GND_13") (pintype "bidirectional"))
      (node (ref "U5") (pin "33") (pinfunction "GND_33") (pintype "bidirectional"))
      (node (ref "U5") (pin "34") (pinfunction "GND_34") (pintype "bidirectional"))
      (node (ref "U5") (pin "GND") (pinfunction "GND_GND") (pintype "bidirectional"))
      (node (ref "U6") (pin "2") (pinfunction "GND_2") (pintype "power_in"))
      (node (ref "U7") (pin "18") (pinfunction "GND_18") (pintype "bidirectional"))
      (node (ref "X1") (pin "2") (pinfunction "GND_2") (pintype "bidirectional"))
      (node (ref "X1") (pin "4") (pinfunction "GND_4") (pintype "bidirectional"))
    )
    (net (code "25") (name "I2C_SCL") (class "Default")
      (node (ref "J3") (pin "17") (pinfunction "17_17") (pintype "bidirectional"))
      (node (ref "J3") (pin "17B") (pinfunction "17_17B") (pintype "bidirectional"))
      (node (ref "U5") (pin "5") (pinfunction "P01/AIN2_5") (pintype "bidirectional"))
    )
    (net (code "26") (name "I2C_SDA") (class "Default")
      (node (ref "J3") (pin "18") (pinfunction "18_18") (pintype "bidirectional"))
      (node (ref "J3") (pin "18B") (pinfunction "18_18B") (pintype "bidirectional"))
      (node (ref "U5") (pin "11") (pinfunction "P07_11") (pintype "bidirectional"))
    )
    (net (code "27") (name "INT") (class "Default")
      (node (ref "JP6") (pin "8") (pinfunction "8_8") (pintype "passive"))
      (node (ref "U7") (pin "12") (pinfunction "INT_12") (pintype "bidirectional"))
    )
    (net (code "28") (name "LED_BLUE") (class "Default")
      (node (ref "R1") (pin "1") (pinfunction "1_1") (pintype "passive"))
      (node (ref "U5") (pin "27") (pinfunction "P19_27") (pintype "bidirectional"))
    )
    (net (code "29") (name "LED_GREEN") (class "Default")
      (node (ref "R2") (pin "1") (pinfunction "1_1") (pintype "passive"))
      (node (ref "U5") (pin "28") (pinfunction "P20_28") (pintype "bidirectional"))
    )
    (net (code "30") (name "LED_RED") (class "Default")
      (node (ref "R3") (pin "1") (pinfunction "1_1") (pintype "passive"))
      (node (ref "U5") (pin "26") (pinfunction "P18_26") (pintype "bidirectional"))
    )
    (net (code "31") (name "Net-(A1-ANTENNA)") (class "Default")
      (node (ref "A1") (pin "1") (pinfunction "ANTENNA_1") (pintype "bidirectional"))
      (node (ref "B1") (pin "SE") (pinfunction "SE_SE") (pintype "bidirectional"))
      (node (ref "C1") (pin "1") (pinfunction "1_1") (pintype "bidirectional"))
    )
    (net (code "32") (name "Net-(B1-VDD_PA)") (class "Default")
      (node (ref "B1") (pin "VCC") (pinfunction "VDD_PA_VCC") (pintype "bidirectional"))
      (node (ref "C8") (pin "1") (pinfunction "1_1") (pintype "bidirectional"))
      (node (ref "U5") (pin "30") (pinfunction "VDD_PA_30") (pintype "bidirectional"))
    )
    (net (code "33") (name "Net-(C13-Pad1)") (class "Default")
      (node (ref "C13") (pin "1") (pinfunction "1_1") (pintype "bidirectional"))
      (node (ref "C6") (pin "1") (pinfunction "1_1") (pintype "bidirectional"))
      (node (ref "L1") (pin "1") (pinfunction "1_1") (pintype "bidirectional"))
      (node (ref "U5") (pin "35") (pinfunction "AVDD_35") (pintype "bidirectional"))
      (node (ref "U5") (pin "36") (pinfunction "AVDD_36") (pintype "bidirectional"))
    )
    (net (code "34") (name "Net-(D1-B)") (class "Default")
      (node (ref "D1") (pin "3") (pinfunction "B_3") (pintype "output"))
      (node (ref "R1") (pin "2") (pinfunction "2_2") (pintype "passive"))
    )
    (net (code "35") (name "Net-(D1-G)") (class "Default")
      (node (ref "D1") (pin "4") (pinfunction "G_4") (pintype "output"))
      (node (ref "R2") (pin "2") (pinfunction "2_2") (pintype "passive"))
    )
    (net (code "36") (name "Net-(D1-R)") (class "Default")
      (node (ref "D1") (pin "2") (pinfunction "R_2") (pintype "output"))
      (node (ref "R3") (pin "2") (pinfunction "2_2") (pintype "passive"))
    )
    (net (code "37") (name "Net-(L1-Pad2)") (class "Default")
      (node (ref "L1") (pin "2") (pinfunction "2_2") (pintype "bidirectional"))
      (node (ref "L3") (pin "1") (pinfunction "1_1") (pintype "bidirectional"))
    )
    (net (code "38") (name "Net-(S1-IN)") (class "Default")
      (node (ref "S1") (pin "C") (pinfunction "IN_C") (pintype "bidirectional"))
      (node (ref "U4") (pin "8") (pinfunction "VSEL4_8") (pintype "bidirectional"))
      (node (ref "U4") (pin "9") (pinfunction "VSEL3_9") (pintype "bidirectional"))
    )
    (net (code "39") (name "Net-(U3-CLKOE)") (class "Default")
      (node (ref "R5") (pin "1") (pinfunction "1_1") (pintype "passive"))
      (node (ref "U3") (pin "1") (pinfunction "CLKOE_1") (pintype "bidirectional"))
    )
    (net (code "40") (name "Net-(U3-VBACKUP)") (class "Default")
      (node (ref "R4") (pin "1") (pinfunction "1_1") (pintype "passive"))
      (node (ref "U3") (pin "9") (pinfunction "VBACKUP_9") (pintype "bidirectional"))
    )
    (net (code "41") (name "Net-(U4-SW)") (class "Default")
      (node (ref "L2") (pin "1") (pinfunction "1_1") (pintype "bidirectional"))
      (node (ref "U4") (pin "2") (pinfunction "SW_2") (pintype "bidirectional"))
    )
    (net (code "42") (name "Net-(U5-ANT1)") (class "Default")
      (node (ref "B1") (pin "ANT1") (pinfunction "ANT1_ANT1") (pintype "bidirectional"))
      (node (ref "U5") (pin "31") (pinfunction "ANT1_31") (pintype "bidirectional"))
    )
    (net (code "43") (name "Net-(U5-ANT2)") (class "Default")
      (node (ref "B1") (pin "ANT2") (pinfunction "ANT2_ANT2") (pintype "bidirectional"))
      (node (ref "U5") (pin "32") (pinfunction "ANT2_32") (pintype "bidirectional"))
    )
    (net (code "44") (name "Net-(U5-DCC)") (class "Default")
      (node (ref "L3") (pin "2") (pinfunction "2_2") (pintype "bidirectional"))
      (node (ref "U5") (pin "2") (pinfunction "DCC_2") (pintype "bidirectional"))
    )
    (net (code "45") (name "Net-(U5-DEC1)") (class "Default")
      (node (ref "C7") (pin "1") (pinfunction "1_1") (pintype "bidirectional"))
      (node (ref "U5") (pin "39") (pinfunction "DEC1_39") (pintype "bidirectional"))
    )
    (net (code "46") (name "Net-(U5-DEC2)") (class "Default")
      (node (ref "C10") (pin "1") (pinfunction "1_1") (pintype "bidirectional"))
      (node (ref "U5") (pin "29") (pinfunction "DEC2_29") (pintype "bidirectional"))
    )
    (net (code "47") (name "Net-(U5-P26{slash}AIN0{slash}XL2)") (class "Default")
      (node (ref "C5") (pin "1") (pinfunction "1_1") (pintype "bidirectional"))
      (node (ref "U5") (pin "45") (pinfunction "P26/AIN0/XL2_45") (pintype "bidirectional"))
      (node (ref "X2") (pin "A") (pinfunction "1_A") (pintype "bidirectional"))
    )
    (net (code "48") (name "Net-(U5-P27{slash}AIN1{slash}XL1)") (class "Default")
      (node (ref "C4") (pin "1") (pinfunction "1_1") (pintype "bidirectional"))
      (node (ref "U5") (pin "46") (pinfunction "P27/AIN1/XL1_46") (pintype "bidirectional"))
      (node (ref "X2") (pin "B") (pinfunction "2_B") (pintype "bidirectional"))
    )
    (net (code "49") (name "Net-(U5-XC1)") (class "Default")
      (node (ref "C3") (pin "1") (pinfunction "1_1") (pintype "bidirectional"))
      (node (ref "U5") (pin "37") (pinfunction "XC1_37") (pintype "bidirectional"))
      (node (ref "X1") (pin "1") (pinfunction "1_1") (pintype "bidirectional"))
    )
    (net (code "50") (name "Net-(U5-XC2)") (class "Default")
      (node (ref "C2") (pin "1") (pinfunction "1_1") (pintype "bidirectional"))
      (node (ref "U5") (pin "38") (pinfunction "XC2_38") (pintype "bidirectional"))
      (node (ref "X1") (pin "3") (pinfunction "2_3") (pintype "bidirectional"))
    )
    (net (code "51") (name "Net-(U7-CPOUT)") (class "Default")
      (node (ref "C23") (pin "1") (pinfunction "1_1") (pintype "passive"))
      (node (ref "U7") (pin "20") (pinfunction "CPOUT_20") (pintype "bidirectional"))
    )
    (net (code "52") (name "Net-(U7-REGOUT)") (class "Default")
      (node (ref "C22") (pin "1") (pinfunction "1_1") (pintype "passive"))
      (node (ref "U7") (pin "10") (pinfunction "REGOUT_10") (pintype "bidirectional"))
    )
    (net (code "53") (name "P08") (class "Default")
      (node (ref "J3") (pin "19") (pinfunction "19_19") (pintype "bidirectional"))
      (node (ref "J3") (pin "19B") (pinfunction "19_19B") (pintype "bidirectional"))
      (node (ref "U5") (pin "14") (pinfunction "P08_14") (pintype "bidirectional"))
    )
    (net (code "54") (name "P09") (class "Default")
      (node (ref "J3") (pin "20") (pinfunction "20_20") (pintype "bidirectional"))
      (node (ref "J3") (pin "20B") (pinfunction "20_20B") (pintype "bidirectional"))
      (node (ref "U5") (pin "15") (pinfunction "P09_15") (pintype "bidirectional"))
    )
    (net (code "55") (name "P10") (class "Default")
      (node (ref "J3") (pin "21") (pinfunction "21_21") (pintype "bidirectional"))
      (node (ref "J3") (pin "21B") (pinfunction "21_21B") (pintype "bidirectional"))
      (node (ref "U5") (pin "16") (pinfunction "P10_16") (pintype "bidirectional"))
    )
    (net (code "56") (name "P17") (class "Default")
      (node (ref "J3") (pin "2") (pinfunction "2_2") (pintype "bidirectional"))
      (node (ref "J3") (pin "2B") (pinfunction "2_2B") (pintype "bidirectional"))
      (node (ref "U5") (pin "25") (pinfunction "P17_25") (pintype "bidirectional"))
    )
    (net (code "57") (name "P21") (class "Default")
      (node (ref "J3") (pin "6") (pinfunction "6_6") (pintype "bidirectional"))
      (node (ref "J3") (pin "6B") (pinfunction "6_6B") (pintype "bidirectional"))
      (node (ref "U5") (pin "40") (pinfunction "P21_40") (pintype "bidirectional"))
    )
    (net (code "58") (name "P22") (class "Default")
      (node (ref "J3") (pin "7") (pinfunction "7_7") (pintype "bidirectional"))
      (node (ref "J3") (pin "7B") (pinfunction "7_7B") (pintype "bidirectional"))
      (node (ref "U5") (pin "41") (pinfunction "P22_41") (pintype "bidirectional"))
    )
    (net (code "59") (name "P23") (class "Default")
      (node (ref "J3") (pin "8") (pinfunction "8_8") (pintype "bidirectional"))
      (node (ref "J3") (pin "8B") (pinfunction "8_8B") (pintype "bidirectional"))
      (node (ref "U5") (pin "42") (pinfunction "P23_42") (pintype "bidirectional"))
    )
    (net (code "60") (name "P24") (class "Default")
      (node (ref "J3") (pin "9") (pinfunction "9_9") (pintype "bidirectional"))
      (node (ref "J3") (pin "9B") (pinfunction "9_9B") (pintype "bidirectional"))
      (node (ref "U5") (pin "43") (pinfunction "P24_43") (pintype "bidirectional"))
    )
    (net (code "61") (name "RTC_CE") (class "Default")
      (node (ref "U3") (pin "8") (pinfunction "CE_8") (pintype "bidirectional"))
      (node (ref "U5") (pin "47") (pinfunction "P28_47") (pintype "bidirectional"))
    )
    (net (code "62") (name "SCL") (class "Default")
      (node (ref "JP6") (pin "6") (pinfunction "6_6") (pintype "passive"))
      (node (ref "R10") (pin "1") (pinfunction "1_1") (pintype "passive"))
      (node (ref "U7") (pin "23") (pinfunction "SCL_23") (pintype "bidirectional"))
    )
    (net (code "63") (name "SCLK") (class "Default")
      (node (ref "IC1") (pin "P$1") (pinfunction "SCLK_P$1") (pintype "input"))
      (node (ref "U2") (pin "2") (pinfunction "1Y_2") (pintype "bidirectional"))
    )
    (net (code "64") (name "SCLK_5V") (class "Default")
      (node (ref "JP1") (pin "4") (pinfunction "4_4") (pintype "passive"))
      (node (ref "U2") (pin "3") (pinfunction "1A_3") (pintype "bidirectional"))
    )
    (net (code "65") (name "SCS") (class "Default")
      (node (ref "IC1") (pin "P$3") (pinfunction "SCS_P$3") (pintype "input"))
      (node (ref "U2") (pin "6") (pinfunction "3Y_6") (pintype "bidirectional"))
    )
    (net (code "66") (name "SCS_5V") (class "Default")
      (node (ref "JP1") (pin "6") (pinfunction "6_6") (pintype "passive"))
      (node (ref "U2") (pin "7") (pinfunction "3A_7") (pintype "bidirectional"))
    )
    (net (code "67") (name "SDA") (class "Default")
      (node (ref "JP6") (pin "5") (pinfunction "5_5") (pintype "passive"))
      (node (ref "R11") (pin "1") (pinfunction "1_1") (pintype "passive"))
      (node (ref "U7") (pin "24") (pinfunction "SDA_24") (pintype "bidirectional"))
    )
    (net (code "68") (name "SI") (class "Default")
      (node (ref "IC1") (pin "P$2") (pinfunction "SI_P$2") (pintype "input"))
      (node (ref "U2") (pin "4") (pinfunction "2Y_4") (pintype "bidirectional"))
    )
    (net (code "69") (name "SI_5V") (class "Default")
      (node (ref "JP1") (pin "5") (pinfunction "5_5") (pintype "passive"))
      (node (ref "U2") (pin "5") (pinfunction "2A_5") (pintype "bidirectional"))
    )
    (net (code "70") (name "SPI_MISO") (class "Default")
      (node (ref "J3") (pin "14") (pinfunction "14_14") (pintype "bidirectional"))
      (node (ref "J3") (pin "14B") (pinfunction "14_14B") (pintype "bidirectional"))
      (node (ref "U1") (pin "2") (pinfunction "SO_2") (pintype "bidirectional"))
      (node (ref "U3") (pin "5") (pinfunction "MISO_5") (pintype "bidirectional"))
      (node (ref "U5") (pin "48") (pinfunction "P29_48") (pintype "bidirectional"))
    )
    (net (code "71") (name "SPI_MOSI") (class "Default")
      (node (ref "J3") (pin "15") (pinfunction "15_15") (pintype "bidirectional"))
      (node (ref "J3") (pin "15B") (pinfunction "15_15B") (pintype "bidirectional"))
      (node (ref "U1") (pin "5") (pinfunction "SI_5") (pintype "bidirectional"))
      (node (ref "U3") (pin "10") (pinfunction "MOSI_10") (pintype "bidirectional"))
      (node (ref "U5") (pin "3") (pinfunction "P30_3") (pintype "bidirectional"))
    )
    (net (code "72") (name "SPI_SCK") (class "Default")
      (node (ref "J3") (pin "16") (pinfunction "16_16") (pintype "bidirectional"))
      (node (ref "J3") (pin "16B") (pinfunction "16_16B") (pintype "bidirectional"))
      (node (ref "U1") (pin "6") (pinfunction "SCK_6") (pintype "bidirectional"))
      (node (ref "U3") (pin "4") (pinfunction "SCL_4") (pintype "bidirectional"))
      (node (ref "U5") (pin "4") (pinfunction "P00/AREF0_4") (pintype "bidirectional"))
    )
    (net (code "73") (name "SWDCLK") (class "Default")
      (node (ref "J1") (pin "4") (pinfunction "SWDCLK_4") (pintype "bidirectional"))
      (node (ref "J3") (pin "4") (pinfunction "4_4") (pintype "bidirectional"))
      (node (ref "J3") (pin "4B") (pinfunction "4_4B") (pintype "bidirectional"))
      (node (ref "R6") (pin "2") (pinfunction "2_2") (pintype "passive"))
      (node (ref "U5") (pin "24") (pinfunction "SWDCLK_24") (pintype "bidirectional"))
    )
    (net (code "74") (name "SWDIO{slash}~{RESET}") (class "Default")
      (node (ref "J1") (pin "2") (pinfunction "SWDIO_2") (pintype "bidirectional"))
      (node (ref "J3") (pin "3") (pinfunction "3_3") (pintype "bidirectional"))
      (node (ref "J3") (pin "30") (pinfunction "30_30") (pintype "bidirectional"))
      (node (ref "J3") (pin "30B") (pinfunction "30_30B") (pintype "bidirectional"))
      (node (ref "J3") (pin "3B") (pinfunction "3_3B") (pintype "bidirectional"))
      (node (ref "U5") (pin "23") (pinfunction "SWDIO/~{RESET}_23") (pintype "bidirectional"))
    )
    (net (code "75") (name "UNUSED1") (class "Default")
      (node (ref "J3") (pin "5") (pinfunction "5_5") (pintype "bidirectional"))
      (node (ref "J3") (pin "5B") (pinfunction "5_5B") (pintype "bidirectional"))
    )
    (net (code "76") (name "UNUSED2") (class "Default")
      (node (ref "J3") (pin "10") (pinfunction "10_10") (pintype "bidirectional"))
      (node (ref "J3") (pin "10B") (pinfunction "10_10B") (pintype "bidirectional"))
    )
    (net (code "77") (name "UNUSED3") (class "Default")
      (node (ref "J3") (pin "11") (pinfunction "11_11") (pintype "bidirectional"))
      (node (ref "J3") (pin "11B") (pinfunction "11_11B") (pintype "bidirectional"))
    )
    (net (code "78") (name "UNUSED4") (class "Default")
      (node (ref "J3") (pin "12") (pinfunction "12_12") (pintype "bidirectional"))
      (node (ref "J3") (pin "12B") (pinfunction "12_12B") (pintype "bidirectional"))
    )
    (net (code "79") (name "UNUSED5") (class "Default")
      (node (ref "J3") (pin "13") (pinfunction "13_13") (pintype "bidirectional"))
      (node (ref "J3") (pin "13B") (pinfunction "13_13B") (pintype "bidirectional"))
    )
    (net (code "80") (name "VCC") (class "Default")
      (node (ref "C11") (pin "1") (pinfunction "1_1") (pintype "bidirectional"))
      (node (ref "C12") (pin "1") (pinfunction "1_1") (pintype "bidirectional"))
      (node (ref "C14") (pin "1") (pinfunction "1_1") (pintype "bidirectional"))
      (node (ref "C16") (pin "1") (pinfunction "1_1") (pintype "bidirectional"))
      (node (ref "C24") (pin "1") (pinfunction "1_1") (pintype "passive"))
      (node (ref "C9") (pin "1") (pinfunction "1_1") (pintype "bidirectional"))
      (node (ref "D1") (pin "1") (pinfunction "VDD_1") (pintype "bidirectional"))
      (node (ref "J1") (pin "1") (pinfunction "VCC_1") (pintype "bidirectional"))
      (node (ref "J3") (pin "1") (pinfunction "1_1") (pintype "bidirectional"))
      (node (ref "J3") (pin "1B") (pinfunction "1_1B") (pintype "bidirectional"))
      (node (ref "JP6") (pin "10") (pinfunction "10_10") (pintype "passive"))
      (node (ref "L2") (pin "2") (pinfunction "2_2") (pintype "bidirectional"))
      (node (ref "R10") (pin "2") (pinfunction "2_2") (pintype "passive"))
      (node (ref "R11") (pin "2") (pinfunction "2_2") (pintype "passive"))
      (node (ref "SJ1") (pin "1") (pinfunction "1_1") (pintype "passive"))
      (node (ref "U1") (pin "8") (pinfunction "VDD_8") (pintype "bidirectional"))
      (node (ref "U3") (pin "2") (pinfunction "VCC_2") (pintype "bidirectional"))
      (node (ref "U4") (pin "5") (pinfunction "VOUT_5") (pintype "bidirectional"))
      (node (ref "U5") (pin "1") (pinfunction "VDD_1") (pintype "bidirectional"))
      (node (ref "U5") (pin "12") (pinfunction "VDD_12") (pintype "bidirectional"))
      (node (ref "U7") (pin "13") (pinfunction "VDD_13") (pintype "bidirectional"))
    )
    (net (code "81") (name "VIN") (class "Default")
      (node (ref "C20") (pin "1") (pinfunction "P$1_1") (pintype "passive"))
      (node (ref "JP1") (pin "1") (pinfunction "1_1") (pintype "passive"))
      (node (ref "U6") (pin "1") (pinfunction "IN_1") (pintype "power_in"))
      (node (ref "U6") (pin "3") (pinfunction "EN_3") (pintype "input"))
    )
    (net (code "82") (name "VIO") (class "Default")
      (node (ref "C25") (pin "1") (pinfunction "1_1") (pintype "passive"))
      (node (ref "JP6") (pin "4") (pinfunction "4_4") (pintype "passive"))
      (node (ref "U7") (pin "8") (pinfunction "VLOGIC_8") (pintype "bidirectional"))
    )
    (net (code "83") (name "unconnected-(J1-SWO-Pad6)") (class "Default")
      (node (ref "J1") (pin "6") (pinfunction "SWO_6") (pintype "bidirectional"))
    )
    (net (code "84") (name "unconnected-(J1-~{RESET}-Pad3)") (class "Default")
      (node (ref "J1") (pin "3") (pinfunction "~{RESET}_3") (pintype "bidirectional"))
    )
    (net (code "85") (name "unconnected-(U3-CLKOUT-Pad3)") (class "Default")
      (node (ref "U3") (pin "3") (pinfunction "CLKOUT_3") (pintype "bidirectional"))
    )
    (net (code "86") (name "unconnected-(U4-LOAD-Pad6)") (class "Default")
      (node (ref "U4") (pin "6") (pinfunction "LOAD_6") (pintype "bidirectional"))
    )
    (net (code "87") (name "unconnected-(U4-PG-Pad7)") (class "Default")
      (node (ref "U4") (pin "7") (pinfunction "PG_7") (pintype "bidirectional"))
    )
    (net (code "88") (name "unconnected-(U6-P4-Pad4)") (class "Default")
      (node (ref "U6") (pin "4") (pinfunction "P4_4") (pintype "bidirectional"))
    )
    (net (code "89") (name "~{FRAM_CS}") (class "Default")
      (node (ref "U1") (pin "1") (pinfunction "~{CS}_1") (pintype "bidirectional"))
      (node (ref "U5") (pin "21") (pinfunction "P15_21") (pintype "bidirectional"))
    )
    (net (code "90") (name "~{FRAM_HOLD}") (class "Default")
      (node (ref "U1") (pin "7") (pinfunction "~{HOLD}_7") (pintype "bidirectional"))
      (node (ref "U5") (pin "20") (pinfunction "P14_20") (pintype "bidirectional"))
    )
    (net (code "91") (name "~{FRAM_WP}") (class "Default")
      (node (ref "U1") (pin "3") (pinfunction "~{WP}_3") (pintype "bidirectional"))
      (node (ref "U5") (pin "22") (pinfunction "P16_22") (pintype "bidirectional"))
    )
    (net (code "92") (name "~{RTC_INT}") (class "Default")
      (node (ref "U3") (pin "7") (pinfunction "~{INT}_7") (pintype "bidirectional"))
      (node (ref "U5") (pin "44") (pinfunction "P25_44") (pintype "bidirectional"))
    )
  )
)
